# node.net
KiCad netlist of a schematic drawn in EAGLE
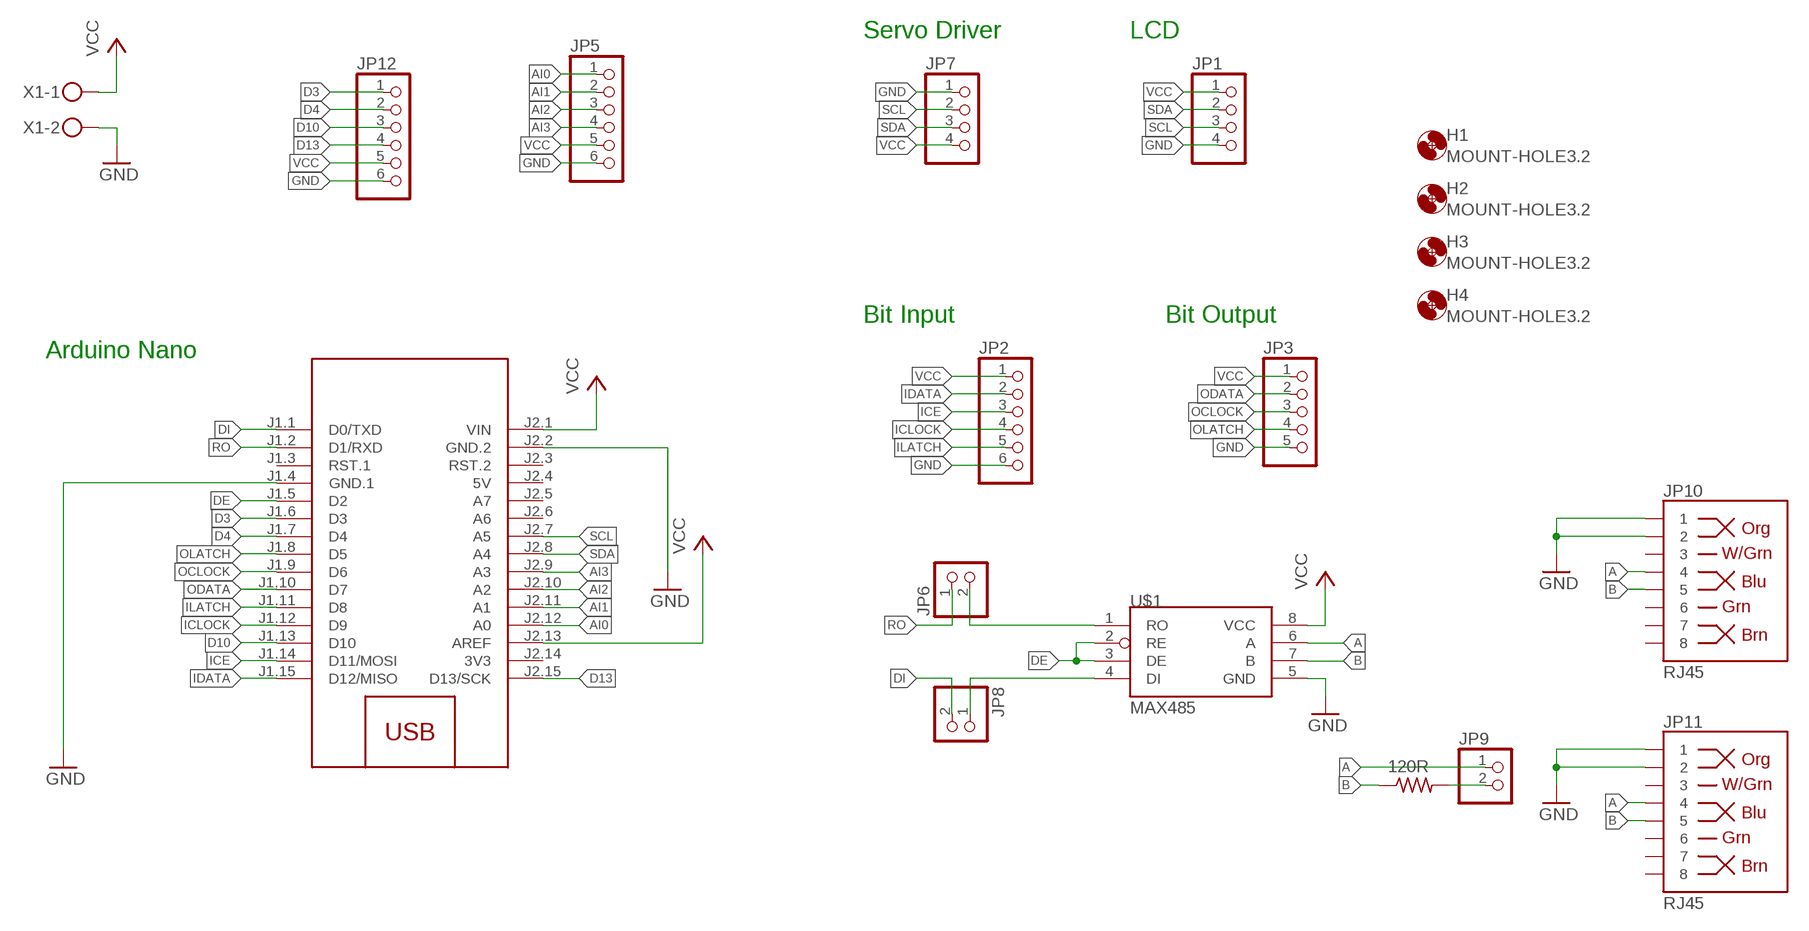
[diagram p0: schematic, sheet 1]

(export (version "E")
  (design (tool "Eeschema 10.0.6"))
  (components
    (comp (ref "H1")
      (value "MOUNT-HOLE3.2")
      (footprint "eagle-import:3,2")
      (libsource (lib "eagle-import") (part "MOUNT-HOLE3.2"))
    )
    (comp (ref "H2")
      (value "MOUNT-HOLE3.2")
      (footprint "eagle-import:3,2")
      (libsource (lib "eagle-import") (part "MOUNT-HOLE3.2"))
    )
    (comp (ref "H3")
      (value "MOUNT-HOLE3.2")
      (footprint "eagle-import:3,2")
      (libsource (lib "eagle-import") (part "MOUNT-HOLE3.2"))
    )
    (comp (ref "H4")
      (value "MOUNT-HOLE3.2")
      (footprint "eagle-import:3,2")
      (libsource (lib "eagle-import") (part "MOUNT-HOLE3.2"))
    )
    (comp (ref "JP1")
      (value "PINHD-1X4/90")
      (footprint "eagle-import:1X04_90")
      (libsource (lib "eagle-import") (part "PINHD-1X4/90"))
    )
    (comp (ref "JP2")
      (value "PINHD-1X6/90")
      (footprint "eagle-import:1X06_90")
      (libsource (lib "eagle-import") (part "PINHD-1X6/90"))
    )
    (comp (ref "JP3")
      (value "PINHD-1X5/90")
      (footprint "eagle-import:1X05_90")
      (libsource (lib "eagle-import") (part "PINHD-1X5/90"))
    )
    (comp (ref "JP5")
      (value "PINHD-1X6")
      (footprint "eagle-import:1X06")
      (libsource (lib "eagle-import") (part "PINHD-1X6"))
    )
    (comp (ref "JP6")
      (value "PINHD-1X2")
      (footprint "eagle-import:1X02")
      (libsource (lib "eagle-import") (part "PINHD-1X2"))
    )
    (comp (ref "JP7")
      (value "PINHD-1X4/90")
      (footprint "eagle-import:1X04_90")
      (libsource (lib "eagle-import") (part "PINHD-1X4/90"))
    )
    (comp (ref "JP8")
      (value "PINHD-1X2")
      (footprint "eagle-import:1X02")
      (libsource (lib "eagle-import") (part "PINHD-1X2"))
    )
    (comp (ref "JP9")
      (value "PINHD-1X2")
      (footprint "eagle-import:1X02")
      (libsource (lib "eagle-import") (part "PINHD-1X2"))
    )
    (comp (ref "JP10")
      (value "RJ45")
      (footprint "eagle-import:RJ45-8")
      (libsource (lib "eagle-import") (part "RJ45-8PTH"))
    )
    (comp (ref "JP11")
      (value "RJ45")
      (footprint "eagle-import:RJ45-8")
      (libsource (lib "eagle-import") (part "RJ45-8PTH"))
    )
    (comp (ref "JP12")
      (value "PINHD-1X6")
      (footprint "eagle-import:1X06")
      (libsource (lib "eagle-import") (part "PINHD-1X6"))
    )
    (comp (ref "M1")
      (value "ARDUINO-NANO-3.0")
      (footprint "eagle-import:ARDUINO-NANO-3.0")
      (libsource (lib "eagle-import") (part "ARDUINO-NANO-3.0"))
    )
    (comp (ref "R2")
      (value "120R")
      (footprint "eagle-import:0207_2V")
      (libsource (lib "eagle-import") (part "R-US_0207/2V"))
    )
    (comp (ref "U$1")
      (value "MAX485")
      (footprint "eagle-import:DIL08")
      (libsource (lib "eagle-import") (part "MAX485DIL"))
    )
    (comp (ref "X1")
      (value "MKDSN1,5/2-5,08")
      (footprint "eagle-import:MKDSN1,5_2-5,08")
      (libsource (lib "eagle-import") (part "MKDSN1,5/2-5,08"))
    )
  )
  (nets
    (net (code "1") (name "/3V3") (class "Default")
      (node (ref "M1") (pin "J2.14") (pinfunction "3V3_J2.14") (pintype "power_in"))
    )
    (net (code "2") (name "/5V") (class "Default")
      (node (ref "M1") (pin "J2.4") (pinfunction "5V_J2.4") (pintype "power_in"))
    )
    (net (code "3") (name "A") (class "Default")
      (node (ref "JP10") (pin "4") (pinfunction "4_4") (pintype "bidirectional"))
      (node (ref "JP11") (pin "4") (pinfunction "4_4") (pintype "bidirectional"))
      (node (ref "JP9") (pin "1") (pinfunction "1_1") (pintype "passive"))
      (node (ref "U$1") (pin "6") (pinfunction "A_6") (pintype "bidirectional"))
    )
    (net (code "4") (name "AI0") (class "Default")
      (node (ref "JP5") (pin "1") (pinfunction "1_1") (pintype "passive"))
      (node (ref "M1") (pin "J2.12") (pinfunction "A0_J2.12") (pintype "bidirectional"))
    )
    (net (code "5") (name "AI1") (class "Default")
      (node (ref "JP5") (pin "2") (pinfunction "2_2") (pintype "passive"))
      (node (ref "M1") (pin "J2.11") (pinfunction "A1_J2.11") (pintype "bidirectional"))
    )
    (net (code "6") (name "AI2") (class "Default")
      (node (ref "JP5") (pin "3") (pinfunction "3_3") (pintype "passive"))
      (node (ref "M1") (pin "J2.10") (pinfunction "A2_J2.10") (pintype "bidirectional"))
    )
    (net (code "7") (name "AI3") (class "Default")
      (node (ref "JP5") (pin "4") (pinfunction "4_4") (pintype "passive"))
      (node (ref "M1") (pin "J2.9") (pinfunction "A3_J2.9") (pintype "bidirectional"))
    )
    (net (code "8") (name "B") (class "Default")
      (node (ref "JP10") (pin "5") (pinfunction "5_5") (pintype "bidirectional"))
      (node (ref "JP11") (pin "5") (pinfunction "5_5") (pintype "bidirectional"))
      (node (ref "R2") (pin "1") (pinfunction "1_1") (pintype "passive"))
      (node (ref "U$1") (pin "7") (pinfunction "B_7") (pintype "bidirectional"))
    )
    (net (code "9") (name "D3") (class "Default")
      (node (ref "JP12") (pin "1") (pinfunction "1_1") (pintype "passive"))
      (node (ref "M1") (pin "J1.6") (pinfunction "D3_J1.6") (pintype "bidirectional"))
    )
    (net (code "10") (name "D4") (class "Default")
      (node (ref "JP12") (pin "2") (pinfunction "2_2") (pintype "passive"))
      (node (ref "M1") (pin "J1.7") (pinfunction "D4_J1.7") (pintype "bidirectional"))
    )
    (net (code "11") (name "D10") (class "Default")
      (node (ref "JP12") (pin "3") (pinfunction "3_3") (pintype "passive"))
      (node (ref "M1") (pin "J1.13") (pinfunction "D10_J1.13") (pintype "bidirectional"))
    )
    (net (code "12") (name "D13") (class "Default")
      (node (ref "JP12") (pin "4") (pinfunction "4_4") (pintype "passive"))
      (node (ref "M1") (pin "J2.15") (pinfunction "D13/SCK_J2.15") (pintype "bidirectional"))
    )
    (net (code "13") (name "DE") (class "Default")
      (node (ref "M1") (pin "J1.5") (pinfunction "D2_J1.5") (pintype "bidirectional"))
      (node (ref "U$1") (pin "2") (pinfunction "RE_2") (pintype "bidirectional"))
      (node (ref "U$1") (pin "3") (pinfunction "DE_3") (pintype "bidirectional"))
    )
    (net (code "14") (name "DI") (class "Default")
      (node (ref "JP8") (pin "2") (pinfunction "2_2") (pintype "passive"))
      (node (ref "M1") (pin "J1.1") (pinfunction "D0/TXD_J1.1") (pintype "bidirectional"))
    )
    (net (code "15") (name "GND") (class "Default")
      (node (ref "JP1") (pin "4") (pinfunction "4_4") (pintype "passive"))
      (node (ref "JP10") (pin "1") (pinfunction "1_1") (pintype "bidirectional"))
      (node (ref "JP10") (pin "2") (pinfunction "2_2") (pintype "bidirectional"))
      (node (ref "JP11") (pin "1") (pinfunction "1_1") (pintype "bidirectional"))
      (node (ref "JP11") (pin "2") (pinfunction "2_2") (pintype "bidirectional"))
      (node (ref "JP12") (pin "6") (pinfunction "6_6") (pintype "passive"))
      (node (ref "JP2") (pin "6") (pinfunction "6_6") (pintype "passive"))
      (node (ref "JP3") (pin "5") (pinfunction "5_5") (pintype "passive"))
      (node (ref "JP5") (pin "6") (pinfunction "6_6") (pintype "passive"))
      (node (ref "JP7") (pin "1") (pinfunction "1_1") (pintype "passive"))
      (node (ref "M1") (pin "J1.4") (pinfunction "GND.1_J1.4") (pintype "power_in"))
      (node (ref "M1") (pin "J2.2") (pinfunction "GND.2_J2.2") (pintype "power_in"))
      (node (ref "U$1") (pin "5") (pinfunction "GND_5") (pintype "bidirectional"))
      (node (ref "X1") (pin "2") (pinfunction "KL_2") (pintype "passive"))
    )
    (net (code "16") (name "ICE") (class "Default")
      (node (ref "JP2") (pin "3") (pinfunction "3_3") (pintype "passive"))
      (node (ref "M1") (pin "J1.14") (pinfunction "D11/MOSI_J1.14") (pintype "bidirectional"))
    )
    (net (code "17") (name "ICLOCK") (class "Default")
      (node (ref "JP2") (pin "4") (pinfunction "4_4") (pintype "passive"))
      (node (ref "M1") (pin "J1.12") (pinfunction "D9_J1.12") (pintype "bidirectional"))
    )
    (net (code "18") (name "IDATA") (class "Default")
      (node (ref "JP2") (pin "2") (pinfunction "2_2") (pintype "passive"))
      (node (ref "M1") (pin "J1.15") (pinfunction "D12/MISO_J1.15") (pintype "bidirectional"))
    )
    (net (code "19") (name "ILATCH") (class "Default")
      (node (ref "JP2") (pin "5") (pinfunction "5_5") (pintype "passive"))
      (node (ref "M1") (pin "J1.11") (pinfunction "D8_J1.11") (pintype "bidirectional"))
    )
    (net (code "20") (name "Net-(JP9-Pad2)") (class "Default")
      (node (ref "JP9") (pin "2") (pinfunction "2_2") (pintype "passive"))
      (node (ref "R2") (pin "2") (pinfunction "2_2") (pintype "passive"))
    )
    (net (code "21") (name "Net-(U$1-DI)") (class "Default")
      (node (ref "JP8") (pin "1") (pinfunction "1_1") (pintype "passive"))
      (node (ref "U$1") (pin "4") (pinfunction "DI_4") (pintype "bidirectional"))
    )
    (net (code "22") (name "Net-(U$1-RO)") (class "Default")
      (node (ref "JP6") (pin "2") (pinfunction "2_2") (pintype "passive"))
      (node (ref "U$1") (pin "1") (pinfunction "RO_1") (pintype "bidirectional"))
    )
    (net (code "23") (name "OCLOCK") (class "Default")
      (node (ref "JP3") (pin "3") (pinfunction "3_3") (pintype "passive"))
      (node (ref "M1") (pin "J1.9") (pinfunction "D6_J1.9") (pintype "bidirectional"))
    )
    (net (code "24") (name "ODATA") (class "Default")
      (node (ref "JP3") (pin "2") (pinfunction "2_2") (pintype "passive"))
      (node (ref "M1") (pin "J1.10") (pinfunction "D7_J1.10") (pintype "bidirectional"))
    )
    (net (code "25") (name "OLATCH") (class "Default")
      (node (ref "JP3") (pin "4") (pinfunction "4_4") (pintype "passive"))
      (node (ref "M1") (pin "J1.8") (pinfunction "D5_J1.8") (pintype "bidirectional"))
    )
    (net (code "26") (name "RO") (class "Default")
      (node (ref "JP6") (pin "1") (pinfunction "1_1") (pintype "passive"))
      (node (ref "M1") (pin "J1.2") (pinfunction "D1/RXD_J1.2") (pintype "bidirectional"))
    )
    (net (code "27") (name "SCL") (class "Default")
      (node (ref "JP1") (pin "3") (pinfunction "3_3") (pintype "passive"))
      (node (ref "JP7") (pin "2") (pinfunction "2_2") (pintype "passive"))
      (node (ref "M1") (pin "J2.7") (pinfunction "A5_J2.7") (pintype "bidirectional"))
    )
    (net (code "28") (name "SDA") (class "Default")
      (node (ref "JP1") (pin "2") (pinfunction "2_2") (pintype "passive"))
      (node (ref "JP7") (pin "3") (pinfunction "3_3") (pintype "passive"))
      (node (ref "M1") (pin "J2.8") (pinfunction "A4_J2.8") (pintype "bidirectional"))
    )
    (net (code "29") (name "VCC") (class "Default")
      (node (ref "JP1") (pin "1") (pinfunction "1_1") (pintype "passive"))
      (node (ref "JP12") (pin "5") (pinfunction "5_5") (pintype "passive"))
      (node (ref "JP2") (pin "1") (pinfunction "1_1") (pintype "passive"))
      (node (ref "JP3") (pin "1") (pinfunction "1_1") (pintype "passive"))
      (node (ref "JP5") (pin "5") (pinfunction "5_5") (pintype "passive"))
      (node (ref "JP7") (pin "4") (pinfunction "4_4") (pintype "passive"))
      (node (ref "M1") (pin "J2.1") (pinfunction "VIN_J2.1") (pintype "power_in"))
      (node (ref "M1") (pin "J2.13") (pinfunction "AREF_J2.13") (pintype "bidirectional"))
      (node (ref "U$1") (pin "8") (pinfunction "VCC_8") (pintype "bidirectional"))
      (node (ref "X1") (pin "1") (pinfunction "KL_1") (pintype "passive"))
    )
    (net (code "30") (name "unconnected-(JP10-Pad3)") (class "Default")
      (node (ref "JP10") (pin "3") (pinfunction "3_3") (pintype "bidirectional"))
    )
    (net (code "31") (name "unconnected-(JP10-Pad6)") (class "Default")
      (node (ref "JP10") (pin "6") (pinfunction "6_6") (pintype "bidirectional"))
    )
    (net (code "32") (name "unconnected-(JP10-Pad7)") (class "Default")
      (node (ref "JP10") (pin "7") (pinfunction "7_7") (pintype "bidirectional"))
    )
    (net (code "33") (name "unconnected-(JP10-Pad8)") (class "Default")
      (node (ref "JP10") (pin "8") (pinfunction "8_8") (pintype "bidirectional"))
    )
    (net (code "34") (name "unconnected-(JP11-Pad3)") (class "Default")
      (node (ref "JP11") (pin "3") (pinfunction "3_3") (pintype "bidirectional"))
    )
    (net (code "35") (name "unconnected-(JP11-Pad6)") (class "Default")
      (node (ref "JP11") (pin "6") (pinfunction "6_6") (pintype "bidirectional"))
    )
    (net (code "36") (name "unconnected-(JP11-Pad7)") (class "Default")
      (node (ref "JP11") (pin "7") (pinfunction "7_7") (pintype "bidirectional"))
    )
    (net (code "37") (name "unconnected-(JP11-Pad8)") (class "Default")
      (node (ref "JP11") (pin "8") (pinfunction "8_8") (pintype "bidirectional"))
    )
    (net (code "38") (name "unconnected-(M1-A6-PadJ2.6)") (class "Default")
      (node (ref "M1") (pin "J2.6") (pinfunction "A6_J2.6") (pintype "bidirectional"))
    )
    (net (code "39") (name "unconnected-(M1-A7-PadJ2.5)") (class "Default")
      (node (ref "M1") (pin "J2.5") (pinfunction "A7_J2.5") (pintype "bidirectional"))
    )
    (net (code "40") (name "unconnected-(M1-RST.1-PadJ1.3)") (class "Default")
      (node (ref "M1") (pin "J1.3") (pinfunction "RST.1_J1.3") (pintype "bidirectional"))
    )
    (net (code "41") (name "unconnected-(M1-RST.2-PadJ2.3)") (class "Default")
      (node (ref "M1") (pin "J2.3") (pinfunction "RST.2_J2.3") (pintype "bidirectional"))
    )
  )
)
